# GainBlock.net
KiCad netlist of a schematic drawn in EAGLE
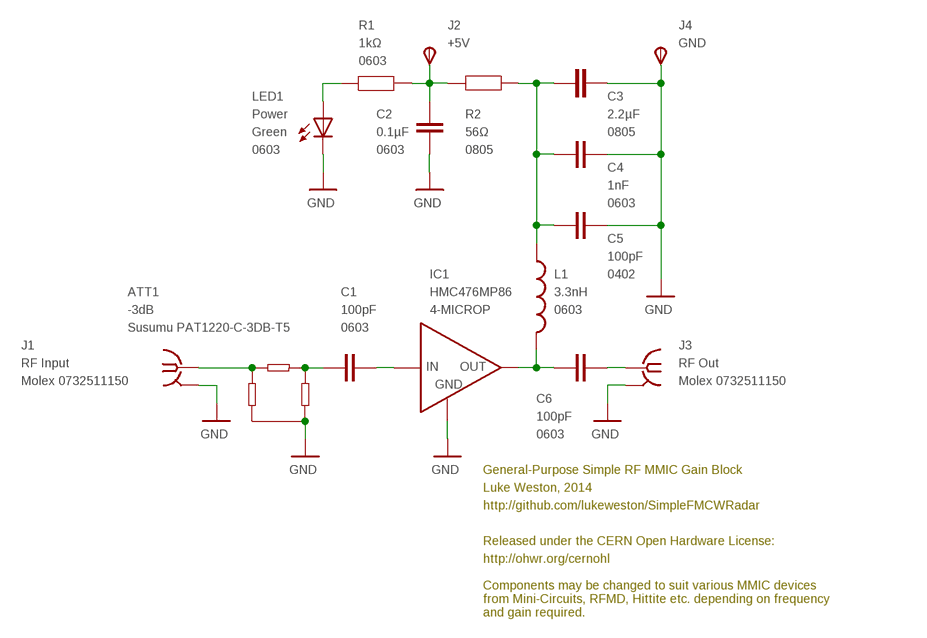
[diagram p0: schematic, sheet 1]

(export (version "E")
  (design (tool "Eeschema 10.0.6"))
  (components
    (comp (ref "ATT1")
      (value "-3dB")
      (footprint "eagle-import:PAT1220")
      (fields (field (name "ID") "Susumu PAT1220-C-3DB-T5"))
      (libsource (lib "eagle-import") (part "PAT1220"))
    )
    (comp (ref "C1")
      (value "100pF")
      (footprint "eagle-import:0603")
      (fields (field (name "PACKAGE") "0603"))
      (libsource (lib "eagle-import") (part "CAPACITOR0603"))
    )
    (comp (ref "C2")
      (value "0.1µF")
      (footprint "eagle-import:0603")
      (fields (field (name "PACKAGE") "0603"))
      (libsource (lib "eagle-import") (part "CAPACITOR0603"))
    )
    (comp (ref "C3")
      (value "2.2µF")
      (footprint "eagle-import:0805")
      (fields (field (name "PACKAGE") "0805") (field (name "VOLTAGE") "10V"))
      (libsource (lib "eagle-import") (part "CAP0805"))
    )
    (comp (ref "C4")
      (value "1nF")
      (footprint "eagle-import:0603")
      (fields (field (name "PACKAGE") "0603"))
      (libsource (lib "eagle-import") (part "CAPACITOR0603"))
    )
    (comp (ref "C5")
      (value "100pF")
      (footprint "eagle-import:0402")
      (fields (field (name "PACKAGE") "0402"))
      (libsource (lib "eagle-import") (part "CAPACITOR0402"))
    )
    (comp (ref "C6")
      (value "100pF")
      (footprint "eagle-import:0603")
      (fields (field (name "PACKAGE") "0603"))
      (libsource (lib "eagle-import") (part "CAPACITOR0603"))
    )
    (comp (ref "IC1")
      (value "HMC476MP86")
      (footprint "eagle-import:WW107")
      (fields (field (name "PACKAGE") "4-MICROP"))
      (libsource (lib "eagle-import") (part "ERA-2SM+"))
    )
    (comp (ref "J1")
      (value "RF Input")
      (footprint "eagle-import:J502-ND-142-0701-881_886")
      (fields
        (field (name "MF") "JOHNSON COMPONENTS")
        (field (name "MPN") "142-0701-881")
        (field (name "ID") "Molex 0732511150")
        (field (name "MF_1") "JOHNSON COMPONENTS")
        (field (name "MPN_1") "142-0701-881")
        (field (name "OC_FARNELL") "1608603")
        (field (name "OC_NEWARK") "08B906")
      )
      (libsource (lib "eagle-import") (part "SMA-142-0701-881/886"))
    )
    (comp (ref "J2")
      (value "TPSPAD1-13")
      (footprint "eagle-import:P1-13")
      (fields (field (name "TP_SIGNAL_NAME") "+5V"))
      (libsource (lib "eagle-import") (part "TPSPAD1-13"))
    )
    (comp (ref "J3")
      (value "RF Out")
      (footprint "eagle-import:J502-ND-142-0701-881_886")
      (fields
        (field (name "MF") "JOHNSON COMPONENTS")
        (field (name "MPN") "142-0701-881")
        (field (name "ID") "Molex 0732511150")
        (field (name "MF_1") "JOHNSON COMPONENTS")
        (field (name "MPN_1") "142-0701-881")
        (field (name "OC_FARNELL") "1608603")
        (field (name "OC_NEWARK") "08B906")
      )
      (libsource (lib "eagle-import") (part "SMA-142-0701-881/886"))
    )
    (comp (ref "J4")
      (value "TPSPAD1-13")
      (footprint "eagle-import:P1-13")
      (fields (field (name "TP_SIGNAL_NAME") "GND"))
      (libsource (lib "eagle-import") (part "TPSPAD1-13"))
    )
    (comp (ref "L1")
      (value "3.3nH")
      (footprint "eagle-import:0603")
      (fields (field (name "ID") "HK160822NJ-T") (field (name "PACKAGE") "0603"))
      (libsource (lib "eagle-import") (part "INDUCTOR0603"))
    )
    (comp (ref "LED1")
      (value "Power")
      (footprint "eagle-import:LED-0603")
      (fields (field (name "COLOR") "Green") (field (name "PACKAGE") "0603"))
      (libsource (lib "eagle-import") (part "LED0603"))
    )
    (comp (ref "R1")
      (value "1kΩ")
      (footprint "eagle-import:0603")
      (fields (field (name "PACKAGE") "0603"))
      (libsource (lib "eagle-import") (part "RESISTOR0603"))
    )
    (comp (ref "R2")
      (value "56Ω")
      (footprint "eagle-import:0805")
      (fields (field (name "PACKAGE") "0805"))
      (libsource (lib "eagle-import") (part "RESISTOR0805"))
    )
  )
  (nets
    (net (code "1") (name "GND") (class "Default")
      (node (ref "ATT1") (pin "3") (pinfunction "3_3") (pintype "bidirectional"))
      (node (ref "C2") (pin "2") (pinfunction "2_2") (pintype "bidirectional"))
      (node (ref "C3") (pin "1") (pinfunction "1_1") (pintype "passive"))
      (node (ref "C4") (pin "2") (pinfunction "2_2") (pintype "bidirectional"))
      (node (ref "C5") (pin "2") (pinfunction "2_2") (pintype "bidirectional"))
      (node (ref "IC1") (pin "2") (pinfunction "GND_2") (pintype "passive"))
      (node (ref "IC1") (pin "4") (pinfunction "GND_4") (pintype "passive"))
      (node (ref "J1") (pin "G@1") (pinfunction "GND_G@1") (pintype "power_in"))
      (node (ref "J3") (pin "G@1") (pinfunction "GND_G@1") (pintype "power_in"))
      (node (ref "J4") (pin "TP") (pinfunction "PP_TP") (pintype "input"))
      (node (ref "LED1") (pin "C") (pinfunction "C_C") (pintype "passive"))
    )
    (net (code "2") (name "Net-(ATT1-Pad1)") (class "Default")
      (node (ref "ATT1") (pin "1") (pinfunction "1_1") (pintype "bidirectional"))
      (node (ref "J1") (pin "1") (pinfunction "1_1") (pintype "passive"))
    )
    (net (code "3") (name "Net-(ATT1-Pad2)") (class "Default")
      (node (ref "ATT1") (pin "2") (pinfunction "2_2") (pintype "bidirectional"))
      (node (ref "C1") (pin "1") (pinfunction "1_1") (pintype "bidirectional"))
    )
    (net (code "4") (name "Net-(C3-Pad2)") (class "Default")
      (node (ref "C3") (pin "2") (pinfunction "2_2") (pintype "passive"))
      (node (ref "C4") (pin "1") (pinfunction "1_1") (pintype "bidirectional"))
      (node (ref "C5") (pin "1") (pinfunction "1_1") (pintype "bidirectional"))
      (node (ref "L1") (pin "1") (pinfunction "1_1") (pintype "passive"))
      (node (ref "R2") (pin "1") (pinfunction "1_1") (pintype "passive"))
    )
    (net (code "5") (name "Net-(C6-Pad2)") (class "Default")
      (node (ref "C6") (pin "2") (pinfunction "2_2") (pintype "bidirectional"))
      (node (ref "J3") (pin "1") (pinfunction "1_1") (pintype "passive"))
    )
    (net (code "6") (name "Net-(IC1-IN)") (class "Default")
      (node (ref "C1") (pin "2") (pinfunction "2_2") (pintype "bidirectional"))
      (node (ref "IC1") (pin "1") (pinfunction "IN_1") (pintype "bidirectional"))
    )
    (net (code "7") (name "Net-(IC1-OUT)") (class "Default")
      (node (ref "C6") (pin "1") (pinfunction "1_1") (pintype "bidirectional"))
      (node (ref "IC1") (pin "3") (pinfunction "OUT_3") (pintype "bidirectional"))
      (node (ref "L1") (pin "2") (pinfunction "2_2") (pintype "passive"))
    )
    (net (code "8") (name "Net-(J2-PP)") (class "Default")
      (node (ref "C2") (pin "1") (pinfunction "1_1") (pintype "bidirectional"))
      (node (ref "J2") (pin "TP") (pinfunction "PP_TP") (pintype "input"))
      (node (ref "R1") (pin "2") (pinfunction "2_2") (pintype "passive"))
      (node (ref "R2") (pin "2") (pinfunction "2_2") (pintype "passive"))
    )
    (net (code "9") (name "Net-(LED1-PadA)") (class "Default")
      (node (ref "LED1") (pin "A") (pinfunction "A_A") (pintype "passive"))
      (node (ref "R1") (pin "1") (pinfunction "1_1") (pintype "passive"))
    )
  )
)
